# Main.net
KiCad netlist of a schematic drawn in Altium Designer
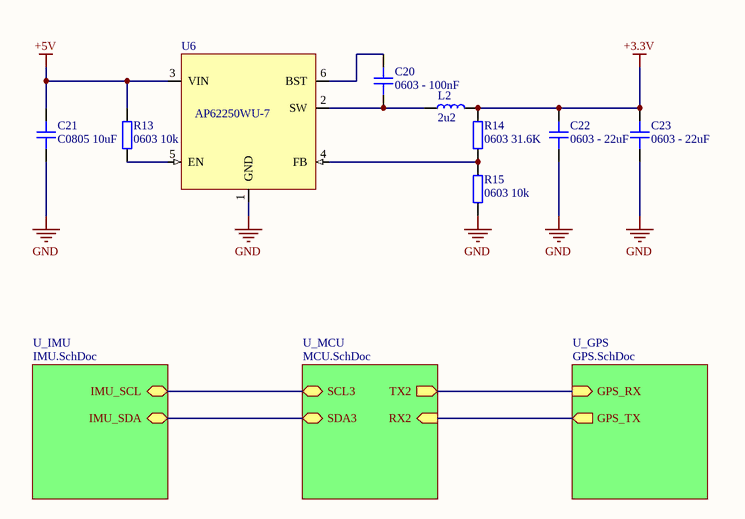
[diagram p0: Main.SchDoc]

(export (version "E")
  (design (tool "Eeschema 10.0.6"))
  (components
    (comp (ref "C20")
      (value "0603 - 100nF")
      (footprint "CAP_0603")
      (description "Capacitor SMD 0603")
      (libsource (lib "Schematic-Lib-PhilsLab") (part "CAP_0603"))
    )
    (comp (ref "C21")
      (value "C0805 10uF")
      (footprint "CAP_0805")
      (description "Capacitor SMD 0805")
      (libsource (lib "Schematic-Lib-PhilsLab") (part "CAP_0805"))
    )
    (comp (ref "C22")
      (value "0603 - 22uF")
      (footprint "CAP_0603")
      (description "Capacitor SMD 0603")
      (libsource (lib "Schematic-Lib-PhilsLab") (part "CAP_0603"))
    )
    (comp (ref "C23")
      (value "0603 - 22uF")
      (footprint "CAP_0603")
      (description "Capacitor SMD 0603")
      (libsource (lib "Schematic-Lib-PhilsLab") (part "CAP_0603"))
    )
    (comp (ref "L2")
      (value "2u2")
      (footprint "SRP0415")
      (description "Inductor SMD 2.2uH Bourns SRP0415-2R2K")
      (fields (field (name "MANUFACTURER") "Bourns") (field (name "MANUFACTURER PART NUMBER") "SRP0415-2R2K"))
      (libsource (lib "Schematic-Lib-PhilsLab") (part "SRP0415-2R2K"))
    )
    (comp (ref "R13")
      (value "0603 10k")
      (footprint "RES_0603")
      (description "Resistor SMD 0603")
      (libsource (lib "Schematic-Lib-PhilsLab") (part "RES_0603"))
    )
    (comp (ref "R14")
      (value "0603 31.6K")
      (footprint "RES_0603")
      (description "Resistor SMD 0603")
      (libsource (lib "Schematic-Lib-PhilsLab") (part "RES_0603"))
    )
    (comp (ref "R15")
      (value "0603 10k")
      (footprint "RES_0603")
      (description "Resistor SMD 0603")
      (libsource (lib "Schematic-Lib-PhilsLab") (part "RES_0603"))
    )
    (comp (ref "U6")
      (value "AP62250WU-7")
      (footprint "TSOT-26-6")
      (description "4.2V TO 18V INPUT, 2.5A LOW IQ SYNCHRONOUS BUCK CONVERTER")
      (fields (field (name "MANUFACTURER") "Diodes Incorporated"))
      (libsource (lib "Schematic-Lib-PhilsLab") (part "AP62250WU-7"))
    )
  )
  (nets
    (net (code "1") (name "+3.3V") (class "Default")
      (node (ref "C22") (pin "2") (pinfunction "2_2") (pintype "passive"))
      (node (ref "C23") (pin "2") (pinfunction "2_2") (pintype "passive"))
      (node (ref "L2") (pin "2") (pinfunction "2_2") (pintype "passive"))
      (node (ref "R14") (pin "2") (pinfunction "2_2") (pintype "passive"))
    )
    (net (code "2") (name "+5V") (class "Default")
      (node (ref "C21") (pin "2") (pinfunction "2_2") (pintype "passive"))
      (node (ref "R13") (pin "2") (pinfunction "2_2") (pintype "passive"))
      (node (ref "U6") (pin "3") (pinfunction "VIN_3") (pintype "power_in"))
    )
    (net (code "7") (name "GND") (class "Default")
      (node (ref "C21") (pin "1") (pinfunction "1_1") (pintype "passive"))
      (node (ref "C22") (pin "1") (pinfunction "1_1") (pintype "passive"))
      (node (ref "C23") (pin "1") (pinfunction "1_1") (pintype "passive"))
      (node (ref "R15") (pin "1") (pinfunction "1_1") (pintype "passive"))
      (node (ref "U6") (pin "1") (pinfunction "GND_1") (pintype "power_in"))
    )
    (net (code "8") (name "Net-(U6-BST)") (class "Default")
      (node (ref "C20") (pin "2") (pinfunction "2_2") (pintype "passive"))
      (node (ref "U6") (pin "6") (pinfunction "BST_6") (pintype "power_in"))
    )
    (net (code "9") (name "Net-(U6-EN)") (class "Default")
      (node (ref "R13") (pin "1") (pinfunction "1_1") (pintype "passive"))
      (node (ref "U6") (pin "5") (pinfunction "EN_5") (pintype "input"))
    )
    (net (code "10") (name "Net-(U6-FB)") (class "Default")
      (node (ref "R14") (pin "1") (pinfunction "1_1") (pintype "passive"))
      (node (ref "R15") (pin "2") (pinfunction "2_2") (pintype "passive"))
      (node (ref "U6") (pin "4") (pinfunction "FB_4") (pintype "input"))
    )
    (net (code "11") (name "Net-(U6-SW)") (class "Default")
      (node (ref "C20") (pin "1") (pinfunction "1_1") (pintype "passive"))
      (node (ref "L2") (pin "1") (pinfunction "1_1") (pintype "passive"))
      (node (ref "U6") (pin "2") (pinfunction "SW_2") (pintype "power_in"))
    )
  )
)
